# MPPT_POWER.net
KiCad netlist of a schematic drawn in Altium Designer
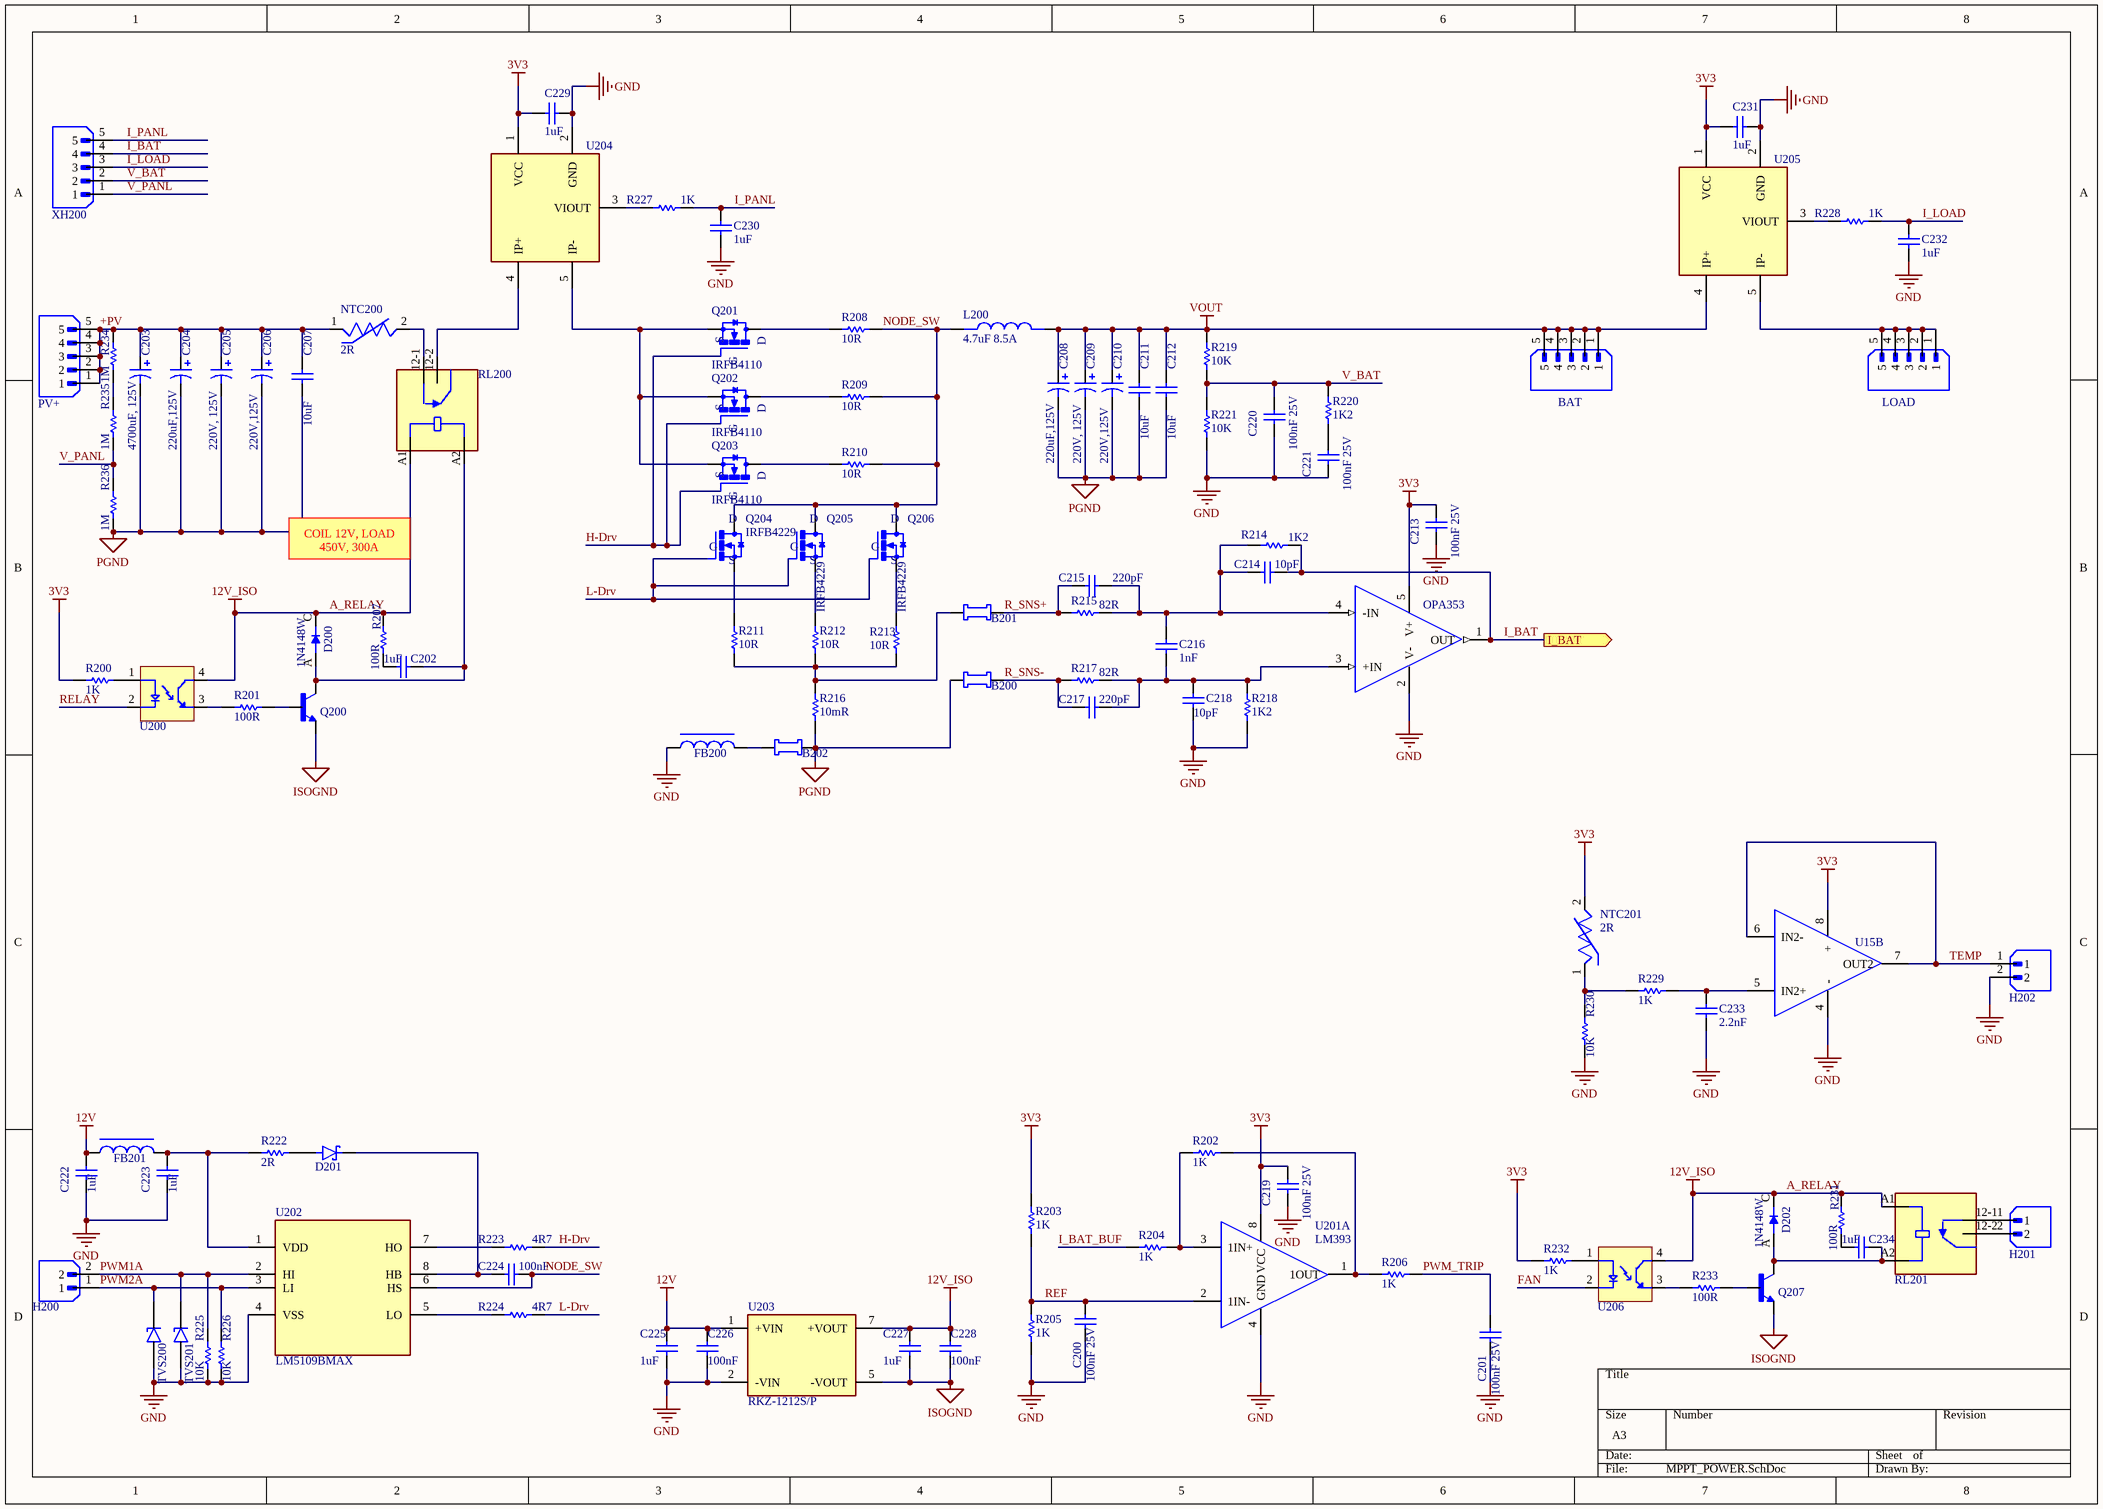
[diagram p0: MPPT_POWER.SchDoc]

(export (version "E")
  (design (tool "Eeschema 10.0.6"))
  (components
    (comp (ref "*") (value "OPA353") (libsource (lib "MPPT_600W") (part "OPA353")))
    (comp (ref "B200")
      (value "Narrow Neck Bridge")
      (footprint "Narrow Bridge")
      (libsource (lib "POWER_PIN_CAMERA") (part "Narrow Neck Bridge"))
    )
    (comp (ref "B201")
      (value "Narrow Neck Bridge")
      (footprint "Narrow Bridge")
      (libsource (lib "POWER_PIN_CAMERA") (part "Narrow Neck Bridge"))
    )
    (comp (ref "B202")
      (value "Narrow Neck Bridge")
      (footprint "Narrow Bridge")
      (libsource (lib "POWER_PIN_CAMERA") (part "Narrow Neck Bridge"))
    )
    (comp (ref "BAT")
      (value "B5B-XH-A(LF)(SN)")
      (footprint "XH2.54 5p")
      (description "Connector Header, XH Series, 5 Position, 2.50mm, Through Hole, Press-Fit, Solder, Natural")
      (fields (field (name "MANUFACTURER") "JST"))
      (libsource (lib "") (part "B5B-XH-A(LF)(SN)_1"))
    )
    (comp (ref "C200")
      (value "100nF 25V")
      (footprint "Cap cer 0603")
      (description "Multilayer Ceramic Capacitor, 0.1 uF, 25 V, ï¿½ 10%, X7R, 0603 [1608 Metric]")
      (fields
        (field (name "MANUFACTURER") "Murata")
        (field (name "MANUFACTURER PART NUMBER") "GCM188R71E104KA57D")
      )
      (libsource (lib "POWER_PIN_CAMERA") (part "GCM188R71E104KA57D"))
    )
    (comp (ref "C201")
      (value "100nF 25V")
      (footprint "Cap cer 0603")
      (description "Multilayer Ceramic Capacitor, 0.1 uF, 25 V, ï¿½ 10%, X7R, 0603 [1608 Metric]")
      (fields
        (field (name "MANUFACTURER") "Murata")
        (field (name "MANUFACTURER PART NUMBER") "GCM188R71E104KA57D")
      )
      (libsource (lib "POWER_PIN_CAMERA") (part "GCM188R71E104KA57D"))
    )
    (comp (ref "C202")
      (value "1uF")
      (footprint "Cap cer 0603")
      (description "Multilayer Ceramic Capacitor, 0.1 uF, 25 V, ï¿½ 10%, X7R, 0603 [1608 Metric]")
      (fields
        (field (name "MANUFACTURER") "Murata")
        (field (name "MANUFACTURER PART NUMBER") "GCM188R71E104KA57D")
      )
      (libsource (lib "POWER_PIN_CAMERA") (part "GCM188R71E104KA57D"))
    )
    (comp (ref "C203")
      (value "4700uF, 125V")
      (footprint "C0805")
      (description "Polarized Capacitor (Surface Mount)")
      (fields (field (name "Comment") "Cap Pol3") (field (name "PUBLISHER") "Altium Limited"))
      (libsource (lib "Miscellaneous Devices") (part "Cap Pol3"))
    )
    (comp (ref "C204")
      (value "220uF,125V")
      (footprint "C0805")
      (description "Polarized Capacitor (Surface Mount)")
      (fields (field (name "Comment") "Cap Pol3") (field (name "PUBLISHER") "Altium Limited"))
      (libsource (lib "Miscellaneous Devices") (part "Cap Pol3"))
    )
    (comp (ref "C205")
      (value "220V, 125V")
      (footprint "C0805")
      (description "Polarized Capacitor (Surface Mount)")
      (fields (field (name "Comment") "Cap Pol3") (field (name "PUBLISHER") "Altium Limited"))
      (libsource (lib "Miscellaneous Devices") (part "Cap Pol3"))
    )
    (comp (ref "C206")
      (value "220V,125V")
      (footprint "C0805")
      (description "Polarized Capacitor (Surface Mount)")
      (fields (field (name "Comment") "Cap Pol3") (field (name "PUBLISHER") "Altium Limited"))
      (libsource (lib "Miscellaneous Devices") (part "Cap Pol3"))
    )
    (comp (ref "C207")
      (value "10uF")
      (footprint "Cap cer 0603")
      (description "Multilayer Ceramic Capacitor, 0.1 uF, 25 V, ï¿½ 10%, X7R, 0603 [1608 Metric]")
      (fields
        (field (name "MANUFACTURER") "Murata")
        (field (name "MANUFACTURER PART NUMBER") "GCM188R71E104KA57D")
      )
      (libsource (lib "POWER_PIN_CAMERA") (part "GCM188R71E104KA57D"))
    )
    (comp (ref "C208")
      (value "220uF,125V")
      (footprint "C0805")
      (description "Polarized Capacitor (Surface Mount)")
      (fields (field (name "Comment") "Cap Pol3") (field (name "PUBLISHER") "Altium Limited"))
      (libsource (lib "Miscellaneous Devices") (part "Cap Pol3"))
    )
    (comp (ref "C209")
      (value "220V, 125V")
      (footprint "C0805")
      (description "Polarized Capacitor (Surface Mount)")
      (fields (field (name "Comment") "Cap Pol3") (field (name "PUBLISHER") "Altium Limited"))
      (libsource (lib "Miscellaneous Devices") (part "Cap Pol3"))
    )
    (comp (ref "C210")
      (value "220V,125V")
      (footprint "C0805")
      (description "Polarized Capacitor (Surface Mount)")
      (fields (field (name "Comment") "Cap Pol3") (field (name "PUBLISHER") "Altium Limited"))
      (libsource (lib "Miscellaneous Devices") (part "Cap Pol3"))
    )
    (comp (ref "C211")
      (value "10uF")
      (footprint "Cap cer 0603")
      (description "Multilayer Ceramic Capacitor, 0.1 uF, 25 V, ï¿½ 10%, X7R, 0603 [1608 Metric]")
      (fields
        (field (name "MANUFACTURER") "Murata")
        (field (name "MANUFACTURER PART NUMBER") "GCM188R71E104KA57D")
      )
      (libsource (lib "POWER_PIN_CAMERA") (part "GCM188R71E104KA57D"))
    )
    (comp (ref "C212")
      (value "10uF")
      (footprint "Cap cer 0603")
      (description "Multilayer Ceramic Capacitor, 0.1 uF, 25 V, ï¿½ 10%, X7R, 0603 [1608 Metric]")
      (fields
        (field (name "MANUFACTURER") "Murata")
        (field (name "MANUFACTURER PART NUMBER") "GCM188R71E104KA57D")
      )
      (libsource (lib "POWER_PIN_CAMERA") (part "GCM188R71E104KA57D"))
    )
    (comp (ref "C213")
      (value "100nF 25V")
      (footprint "Cap cer 0603")
      (description "Multilayer Ceramic Capacitor, 0.1 uF, 25 V, ï¿½ 10%, X7R, 0603 [1608 Metric]")
      (fields
        (field (name "MANUFACTURER") "Murata")
        (field (name "MANUFACTURER PART NUMBER") "GCM188R71E104KA57D")
      )
      (libsource (lib "POWER_PIN_CAMERA") (part "GCM188R71E104KA57D"))
    )
    (comp (ref "C214")
      (value "10pF")
      (footprint "Cap cer 0603")
      (description "Multilayer Ceramic Capacitor, 0.1 uF, 25 V, ï¿½ 10%, X7R, 0603 [1608 Metric]")
      (fields
        (field (name "MANUFACTURER") "Murata")
        (field (name "MANUFACTURER PART NUMBER") "GCM188R71E104KA57D")
      )
      (libsource (lib "POWER_PIN_CAMERA") (part "GCM188R71E104KA57D"))
    )
    (comp (ref "C215")
      (value "220pF")
      (footprint "Cap cer 0603")
      (description "Multilayer Ceramic Capacitor, 0.1 uF, 25 V, ï¿½ 10%, X7R, 0603 [1608 Metric]")
      (fields
        (field (name "MANUFACTURER") "Murata")
        (field (name "MANUFACTURER PART NUMBER") "GCM188R71E104KA57D")
      )
      (libsource (lib "POWER_PIN_CAMERA") (part "GCM188R71E104KA57D"))
    )
    (comp (ref "C216")
      (value "1nF")
      (footprint "Cap cer 0603")
      (description "Multilayer Ceramic Capacitor, 0.1 uF, 25 V, ï¿½ 10%, X7R, 0603 [1608 Metric]")
      (fields
        (field (name "MANUFACTURER") "Murata")
        (field (name "MANUFACTURER PART NUMBER") "GCM188R71E104KA57D")
      )
      (libsource (lib "POWER_PIN_CAMERA") (part "GCM188R71E104KA57D"))
    )
    (comp (ref "C217")
      (value "220pF")
      (footprint "Cap cer 0603")
      (description "Multilayer Ceramic Capacitor, 0.1 uF, 25 V, ï¿½ 10%, X7R, 0603 [1608 Metric]")
      (fields
        (field (name "MANUFACTURER") "Murata")
        (field (name "MANUFACTURER PART NUMBER") "GCM188R71E104KA57D")
      )
      (libsource (lib "POWER_PIN_CAMERA") (part "GCM188R71E104KA57D"))
    )
    (comp (ref "C218")
      (value "10pF")
      (footprint "Cap cer 0603")
      (description "Multilayer Ceramic Capacitor, 0.1 uF, 25 V, ï¿½ 10%, X7R, 0603 [1608 Metric]")
      (fields
        (field (name "MANUFACTURER") "Murata")
        (field (name "MANUFACTURER PART NUMBER") "GCM188R71E104KA57D")
      )
      (libsource (lib "POWER_PIN_CAMERA") (part "GCM188R71E104KA57D"))
    )
    (comp (ref "C219")
      (value "100nF 25V")
      (footprint "Cap cer 0603")
      (description "Multilayer Ceramic Capacitor, 0.1 uF, 25 V, ï¿½ 10%, X7R, 0603 [1608 Metric]")
      (fields
        (field (name "MANUFACTURER") "Murata")
        (field (name "MANUFACTURER PART NUMBER") "GCM188R71E104KA57D")
      )
      (libsource (lib "POWER_PIN_CAMERA") (part "GCM188R71E104KA57D"))
    )
    (comp (ref "C220")
      (value "100nF 25V")
      (footprint "Cap cer 0603")
      (description "Multilayer Ceramic Capacitor, 0.1 uF, 25 V, ï¿½ 10%, X7R, 0603 [1608 Metric]")
      (fields
        (field (name "MANUFACTURER") "Murata")
        (field (name "MANUFACTURER PART NUMBER") "GCM188R71E104KA57D")
      )
      (libsource (lib "POWER_PIN_CAMERA") (part "GCM188R71E104KA57D"))
    )
    (comp (ref "C221")
      (value "100nF 25V")
      (footprint "Cap cer 0603")
      (description "Multilayer Ceramic Capacitor, 0.1 uF, 25 V, ï¿½ 10%, X7R, 0603 [1608 Metric]")
      (fields
        (field (name "MANUFACTURER") "Murata")
        (field (name "MANUFACTURER PART NUMBER") "GCM188R71E104KA57D")
      )
      (libsource (lib "POWER_PIN_CAMERA") (part "GCM188R71E104KA57D"))
    )
    (comp (ref "C222")
      (value "1uF")
      (footprint "Cap cer 0603")
      (description "Multilayer Ceramic Capacitor, 0.1 uF, 25 V, ï¿½ 10%, X7R, 0603 [1608 Metric]")
      (fields
        (field (name "MANUFACTURER") "Murata")
        (field (name "MANUFACTURER PART NUMBER") "GCM188R71E104KA57D")
      )
      (libsource (lib "POWER_PIN_CAMERA") (part "GCM188R71E104KA57D"))
    )
    (comp (ref "C223")
      (value "1uF")
      (footprint "Cap cer 0603")
      (description "Multilayer Ceramic Capacitor, 0.1 uF, 25 V, ï¿½ 10%, X7R, 0603 [1608 Metric]")
      (fields
        (field (name "MANUFACTURER") "Murata")
        (field (name "MANUFACTURER PART NUMBER") "GCM188R71E104KA57D")
      )
      (libsource (lib "POWER_PIN_CAMERA") (part "GCM188R71E104KA57D"))
    )
    (comp (ref "C224")
      (value "100nF")
      (footprint "Cap cer 0603")
      (description "Multilayer Ceramic Capacitor, 0.1 uF, 25 V, ï¿½ 10%, X7R, 0603 [1608 Metric]")
      (fields
        (field (name "MANUFACTURER") "Murata")
        (field (name "MANUFACTURER PART NUMBER") "GCM188R71E104KA57D")
      )
      (libsource (lib "POWER_PIN_CAMERA") (part "GCM188R71E104KA57D"))
    )
    (comp (ref "C225")
      (value "1uF")
      (footprint "Cap cer 0603")
      (description "Multilayer Ceramic Capacitor, 0.1 uF, 25 V, ï¿½ 10%, X7R, 0603 [1608 Metric]")
      (fields
        (field (name "MANUFACTURER") "Murata")
        (field (name "MANUFACTURER PART NUMBER") "GCM188R71E104KA57D")
      )
      (libsource (lib "POWER_PIN_CAMERA") (part "GCM188R71E104KA57D"))
    )
    (comp (ref "C226")
      (value "100nF")
      (footprint "Cap cer 0603")
      (description "Multilayer Ceramic Capacitor, 0.1 uF, 25 V, ï¿½ 10%, X7R, 0603 [1608 Metric]")
      (fields
        (field (name "MANUFACTURER") "Murata")
        (field (name "MANUFACTURER PART NUMBER") "GCM188R71E104KA57D")
      )
      (libsource (lib "POWER_PIN_CAMERA") (part "GCM188R71E104KA57D"))
    )
    (comp (ref "C227")
      (value "1uF")
      (footprint "Cap cer 0603")
      (description "Multilayer Ceramic Capacitor, 0.1 uF, 25 V, ï¿½ 10%, X7R, 0603 [1608 Metric]")
      (fields
        (field (name "MANUFACTURER") "Murata")
        (field (name "MANUFACTURER PART NUMBER") "GCM188R71E104KA57D")
      )
      (libsource (lib "POWER_PIN_CAMERA") (part "GCM188R71E104KA57D"))
    )
    (comp (ref "C228")
      (value "100nF")
      (footprint "Cap cer 0603")
      (description "Multilayer Ceramic Capacitor, 0.1 uF, 25 V, ï¿½ 10%, X7R, 0603 [1608 Metric]")
      (fields
        (field (name "MANUFACTURER") "Murata")
        (field (name "MANUFACTURER PART NUMBER") "GCM188R71E104KA57D")
      )
      (libsource (lib "POWER_PIN_CAMERA") (part "GCM188R71E104KA57D"))
    )
    (comp (ref "C229")
      (value "1uF")
      (footprint "Cap cer 0603")
      (description "Multilayer Ceramic Capacitor, 0.1 uF, 25 V, ï¿½ 10%, X7R, 0603 [1608 Metric]")
      (fields
        (field (name "MANUFACTURER") "Murata")
        (field (name "MANUFACTURER PART NUMBER") "GCM188R71E104KA57D")
      )
      (libsource (lib "POWER_PIN_CAMERA") (part "GCM188R71E104KA57D"))
    )
    (comp (ref "C230")
      (value "1uF")
      (footprint "Cap cer 0603")
      (description "Multilayer Ceramic Capacitor, 0.1 uF, 25 V, ï¿½ 10%, X7R, 0603 [1608 Metric]")
      (fields
        (field (name "MANUFACTURER") "Murata")
        (field (name "MANUFACTURER PART NUMBER") "GCM188R71E104KA57D")
      )
      (libsource (lib "POWER_PIN_CAMERA") (part "GCM188R71E104KA57D"))
    )
    (comp (ref "C231")
      (value "1uF")
      (footprint "Cap cer 0603")
      (description "Multilayer Ceramic Capacitor, 0.1 uF, 25 V, ï¿½ 10%, X7R, 0603 [1608 Metric]")
      (fields
        (field (name "MANUFACTURER") "Murata")
        (field (name "MANUFACTURER PART NUMBER") "GCM188R71E104KA57D")
      )
      (libsource (lib "POWER_PIN_CAMERA") (part "GCM188R71E104KA57D"))
    )
    (comp (ref "C232")
      (value "1uF")
      (footprint "Cap cer 0603")
      (description "Multilayer Ceramic Capacitor, 0.1 uF, 25 V, ï¿½ 10%, X7R, 0603 [1608 Metric]")
      (fields
        (field (name "MANUFACTURER") "Murata")
        (field (name "MANUFACTURER PART NUMBER") "GCM188R71E104KA57D")
      )
      (libsource (lib "POWER_PIN_CAMERA") (part "GCM188R71E104KA57D"))
    )
    (comp (ref "C233")
      (value "2.2nF")
      (footprint "Cap cer 0603")
      (description "Multilayer Ceramic Capacitor, 0.1 uF, 25 V, ï¿½ 10%, X7R, 0603 [1608 Metric]")
      (fields
        (field (name "MANUFACTURER") "Murata")
        (field (name "MANUFACTURER PART NUMBER") "GCM188R71E104KA57D")
      )
      (libsource (lib "POWER_PIN_CAMERA") (part "GCM188R71E104KA57D"))
    )
    (comp (ref "C234")
      (value "1uF")
      (footprint "Cap cer 0603")
      (description "Multilayer Ceramic Capacitor, 0.1 uF, 25 V, ï¿½ 10%, X7R, 0603 [1608 Metric]")
      (fields
        (field (name "MANUFACTURER") "Murata")
        (field (name "MANUFACTURER PART NUMBER") "GCM188R71E104KA57D")
      )
      (libsource (lib "POWER_PIN_CAMERA") (part "GCM188R71E104KA57D"))
    )
    (comp (ref "D200")
      (value "1N4148W")
      (footprint "1N4148")
      (description "Small Signal Diode, Single, 100 V, 300 Ma, 1.25 V, 4 Ns, 2 A Rohs Compliant: Yes")
      (fields (field (name "MANUFACTURER") "Diodes") (field (name "MANUFACTURER PART NUMBER") "1N4148W-7-F"))
      (libsource (lib "POWER_PIN_CAMERA") (part "1N4148W-7-F"))
    )
    (comp (ref "D201")
      (value "B340A-13-F")
      (footprint "B340A")
      (description "Schottky Diode, 3A, 40V, DO-214AC")
      (fields (field (name "MANUFACTURER") "Diodes") (field (name "VOLTAGE") "40V"))
      (libsource (lib "MPPT_600W") (part "B340A-13-F"))
    )
    (comp (ref "D202")
      (value "1N4148W")
      (footprint "1N4148")
      (description "Small Signal Diode, Single, 100 V, 300 Ma, 1.25 V, 4 Ns, 2 A Rohs Compliant: Yes")
      (fields (field (name "MANUFACTURER") "Diodes") (field (name "MANUFACTURER PART NUMBER") "1N4148W-7-F"))
      (libsource (lib "POWER_PIN_CAMERA") (part "1N4148W-7-F"))
    )
    (comp (ref "FB200")
      (value "Ferrite Beads Multi-Layer 390Ohm 25% 100MHz 500mA 300mOhm DCR 0603 Automotive T/R")
      (footprint "FERRITE BEAD 0603")
      (fields
        (field (name "MANUFACTURER") "Murata")
        (field (name "MANUFACTURER PART NUMBER") "BLM18EG391TH1D")
        (field (name "TOLERANCE") "25%")
      )
      (libsource (lib "MPPT_600W") (part "Ferrite Bead"))
    )
    (comp (ref "FB201")
      (value "Ferrite Beads Multi-Layer 390Ohm 25% 100MHz 500mA 300mOhm DCR 0603 Automotive T/R")
      (footprint "FERRITE BEAD 0603")
      (fields
        (field (name "MANUFACTURER") "Murata")
        (field (name "MANUFACTURER PART NUMBER") "BLM18EG391TH1D")
        (field (name "TOLERANCE") "25%")
      )
      (libsource (lib "MPPT_600W") (part "Ferrite Bead"))
    )
    (comp (ref "H200")
      (value "HEADER 2P 2.54")
      (footprint "HEADER 2P 2.544")
      (description "CONNECTOR HEADER, XH SERIES, 2 POSITION, 2.50MM, Press-Fit Solder, Detent Lock, Natural")
      (fields
        (field (name "MANUFACTURER") "JST")
        (field (name "MANUFACTURER PART NUMBER") "B2B-XH-A(LF)(SN)")
      )
      (libsource (lib "MPPT_600W") (part "B2B-XH-A(LF)(SN)"))
    )
    (comp (ref "H201")
      (value "HEADER 2P 2.54")
      (footprint "HEADER 2P 2.544")
      (description "CONNECTOR HEADER, XH SERIES, 2 POSITION, 2.50MM, Press-Fit Solder, Detent Lock, Natural")
      (fields
        (field (name "MANUFACTURER") "JST")
        (field (name "MANUFACTURER PART NUMBER") "B2B-XH-A(LF)(SN)")
      )
      (libsource (lib "") (part "B2B-XH-A(LF)(SN)_1"))
    )
    (comp (ref "H202")
      (value "HEADER 2P 2.54")
      (footprint "HEADER 2P 2.544")
      (description "CONNECTOR HEADER, XH SERIES, 2 POSITION, 2.50MM, Press-Fit Solder, Detent Lock, Natural")
      (fields
        (field (name "MANUFACTURER") "JST")
        (field (name "MANUFACTURER PART NUMBER") "B2B-XH-A(LF)(SN)")
      )
      (libsource (lib "") (part "B2B-XH-A(LF)(SN)_1"))
    )
    (comp (ref "L200")
      (value "4.7uF 8.5A")
      (footprint "Inductor 4.7uF 8.5A")
      (description "FIXED IND 4.7UH 8.5A 18.4MOHM")
      (fields
        (field (name "MANUFACTURER") "Abracon")
        (field (name "MANUFACTURER PART NUMBER") "ASPIAIG-F6050-4R7M-T")
      )
      (libsource (lib "POWER_PIN_CAMERA") (part "Inductor 4.7uF 8.5A"))
    )
    (comp (ref "LOAD")
      (value "B5B-XH-A(LF)(SN)")
      (footprint "XH2.54 5p")
      (description "Connector Header, XH Series, 5 Position, 2.50mm, Through Hole, Press-Fit, Solder, Natural")
      (fields (field (name "MANUFACTURER") "JST"))
      (libsource (lib "") (part "B5B-XH-A(LF)(SN)_1"))
    )
    (comp (ref "NTC200") (value "2R") (libsource (lib "MPPT_600W") (part "NTC")))
    (comp (ref "NTC201") (value "2R") (libsource (lib "MPPT_600W") (part "NTC")))
    (comp (ref "PV+")
      (value "B5B-XH-A(LF)(SN)")
      (footprint "XH2.54 5p")
      (description "Connector Header, XH Series, 5 Position, 2.50mm, Through Hole, Press-Fit, Solder, Natural")
      (fields (field (name "MANUFACTURER") "JST"))
      (libsource (lib "MPPT_600W") (part "B5B-XH-A(LF)(SN)"))
    )
    (comp (ref "Q200")
      (value "MMBT3904")
      (footprint "MMBT3904")
      (description "MMBT3904 Series 40 V CE Breakdown 0.2 A NPN General Purpose Amplifier - SOT-23")
      (fields (field (name "MANUFACTURER") "onsemi"))
      (libsource (lib "MPPT_600W") (part "MMBT3904"))
    )
    (comp (ref "Q201") (value "IRFB4110") (libsource (lib "MPPT_600W") (part "MOSFET")))
    (comp (ref "Q202") (value "IRFB4110") (libsource (lib "MPPT_600W") (part "MOSFET")))
    (comp (ref "Q203") (value "IRFB4110") (libsource (lib "MPPT_600W") (part "MOSFET")))
    (comp (ref "Q204") (value "IRFB4229") (libsource (lib "MPPT_600W") (part "MOSFET")))
    (comp (ref "Q205") (value "IRFB4229") (libsource (lib "MPPT_600W") (part "MOSFET")))
    (comp (ref "Q206") (value "IRFB4229") (libsource (lib "MPPT_600W") (part "MOSFET")))
    (comp (ref "Q207")
      (value "MMBT3904")
      (footprint "MMBT3904")
      (description "MMBT3904 Series 40 V CE Breakdown 0.2 A NPN General Purpose Amplifier - SOT-23")
      (fields (field (name "MANUFACTURER") "onsemi"))
      (libsource (lib "MPPT_600W") (part "MMBT3904"))
    )
    (comp (ref "R200")
      (value "1K")
      (footprint "Res 0603")
      (description "Res Thick Film 0603 2.2K Ohm 5% 1/10W ±200ppm/°C Molded SMD SMD Paper T/R")
      (fields
        (field (name "MANUFACTURER") "Vishay")
        (field (name "MANUFACTURER PART NUMBER") "CRCW06032K20JNEA")
      )
      (libsource (lib "POWER_PIN_CAMERA") (part "Resistor 2.2K"))
    )
    (comp (ref "R201")
      (value "100R")
      (footprint "Res 0603")
      (description "Res Thick Film 0603 2.2K Ohm 5% 1/10W ±200ppm/°C Molded SMD SMD Paper T/R")
      (fields
        (field (name "MANUFACTURER") "Vishay")
        (field (name "MANUFACTURER PART NUMBER") "CRCW06032K20JNEA")
      )
      (libsource (lib "POWER_PIN_CAMERA") (part "Resistor 2.2K"))
    )
    (comp (ref "R202")
      (value "1K")
      (footprint "Res 0603")
      (description "Res Thick Film 0603 2.2K Ohm 5% 1/10W ±200ppm/°C Molded SMD SMD Paper T/R")
      (fields
        (field (name "MANUFACTURER") "Vishay")
        (field (name "MANUFACTURER PART NUMBER") "CRCW06032K20JNEA")
      )
      (libsource (lib "POWER_PIN_CAMERA") (part "Resistor 2.2K"))
    )
    (comp (ref "R203")
      (value "1K")
      (footprint "Res 0603")
      (description "Res Thick Film 0603 2.2K Ohm 5% 1/10W ±200ppm/°C Molded SMD SMD Paper T/R")
      (fields
        (field (name "MANUFACTURER") "Vishay")
        (field (name "MANUFACTURER PART NUMBER") "CRCW06032K20JNEA")
      )
      (libsource (lib "POWER_PIN_CAMERA") (part "Resistor 2.2K"))
    )
    (comp (ref "R204")
      (value "1K")
      (footprint "Res 0603")
      (description "Res Thick Film 0603 2.2K Ohm 5% 1/10W ±200ppm/°C Molded SMD SMD Paper T/R")
      (fields
        (field (name "MANUFACTURER") "Vishay")
        (field (name "MANUFACTURER PART NUMBER") "CRCW06032K20JNEA")
      )
      (libsource (lib "POWER_PIN_CAMERA") (part "Resistor 2.2K"))
    )
    (comp (ref "R205")
      (value "1K")
      (footprint "Res 0603")
      (description "Res Thick Film 0603 2.2K Ohm 5% 1/10W ±200ppm/°C Molded SMD SMD Paper T/R")
      (fields
        (field (name "MANUFACTURER") "Vishay")
        (field (name "MANUFACTURER PART NUMBER") "CRCW06032K20JNEA")
      )
      (libsource (lib "POWER_PIN_CAMERA") (part "Resistor 2.2K"))
    )
    (comp (ref "R206")
      (value "1K")
      (footprint "Res 0603")
      (description "Res Thick Film 0603 2.2K Ohm 5% 1/10W ±200ppm/°C Molded SMD SMD Paper T/R")
      (fields
        (field (name "MANUFACTURER") "Vishay")
        (field (name "MANUFACTURER PART NUMBER") "CRCW06032K20JNEA")
      )
      (libsource (lib "POWER_PIN_CAMERA") (part "Resistor 2.2K"))
    )
    (comp (ref "R207")
      (value "100R")
      (footprint "Res 0603")
      (description "Res Thick Film 0603 2.2K Ohm 5% 1/10W ±200ppm/°C Molded SMD SMD Paper T/R")
      (fields
        (field (name "MANUFACTURER") "Vishay")
        (field (name "MANUFACTURER PART NUMBER") "CRCW06032K20JNEA")
      )
      (libsource (lib "POWER_PIN_CAMERA") (part "Resistor 2.2K"))
    )
    (comp (ref "R208")
      (value "10R")
      (footprint "Res 0603")
      (description "Res Thick Film 0603 2.2K Ohm 5% 1/10W ±200ppm/°C Molded SMD SMD Paper T/R")
      (fields
        (field (name "MANUFACTURER") "Vishay")
        (field (name "MANUFACTURER PART NUMBER") "CRCW06032K20JNEA")
      )
      (libsource (lib "POWER_PIN_CAMERA") (part "Resistor 2.2K"))
    )
    (comp (ref "R209")
      (value "10R")
      (footprint "Res 0603")
      (description "Res Thick Film 0603 2.2K Ohm 5% 1/10W ±200ppm/°C Molded SMD SMD Paper T/R")
      (fields
        (field (name "MANUFACTURER") "Vishay")
        (field (name "MANUFACTURER PART NUMBER") "CRCW06032K20JNEA")
      )
      (libsource (lib "POWER_PIN_CAMERA") (part "Resistor 2.2K"))
    )
    (comp (ref "R210")
      (value "10R")
      (footprint "Res 0603")
      (description "Res Thick Film 0603 2.2K Ohm 5% 1/10W ±200ppm/°C Molded SMD SMD Paper T/R")
      (fields
        (field (name "MANUFACTURER") "Vishay")
        (field (name "MANUFACTURER PART NUMBER") "CRCW06032K20JNEA")
      )
      (libsource (lib "POWER_PIN_CAMERA") (part "Resistor 2.2K"))
    )
    (comp (ref "R211")
      (value "10R")
      (footprint "Res 0603")
      (description "Res Thick Film 0603 2.2K Ohm 5% 1/10W ±200ppm/°C Molded SMD SMD Paper T/R")
      (fields
        (field (name "MANUFACTURER") "Vishay")
        (field (name "MANUFACTURER PART NUMBER") "CRCW06032K20JNEA")
      )
      (libsource (lib "POWER_PIN_CAMERA") (part "Resistor 2.2K"))
    )
    (comp (ref "R212")
      (value "10R")
      (footprint "Res 0603")
      (description "Res Thick Film 0603 2.2K Ohm 5% 1/10W ±200ppm/°C Molded SMD SMD Paper T/R")
      (fields
        (field (name "MANUFACTURER") "Vishay")
        (field (name "MANUFACTURER PART NUMBER") "CRCW06032K20JNEA")
      )
      (libsource (lib "POWER_PIN_CAMERA") (part "Resistor 2.2K"))
    )
    (comp (ref "R213")
      (value "10R")
      (footprint "Res 0603")
      (description "Res Thick Film 0603 2.2K Ohm 5% 1/10W ±200ppm/°C Molded SMD SMD Paper T/R")
      (fields
        (field (name "MANUFACTURER") "Vishay")
        (field (name "MANUFACTURER PART NUMBER") "CRCW06032K20JNEA")
      )
      (libsource (lib "POWER_PIN_CAMERA") (part "Resistor 2.2K"))
    )
    (comp (ref "R214")
      (value "1K2")
      (footprint "Res 0603")
      (description "Res Thick Film 0603 2.2K Ohm 5% 1/10W ±200ppm/°C Molded SMD SMD Paper T/R")
      (fields
        (field (name "MANUFACTURER") "Vishay")
        (field (name "MANUFACTURER PART NUMBER") "CRCW06032K20JNEA")
      )
      (libsource (lib "POWER_PIN_CAMERA") (part "Resistor 2.2K"))
    )
    (comp (ref "R215")
      (value "82R")
      (footprint "Res 0603")
      (description "Res Thick Film 0603 2.2K Ohm 5% 1/10W ±200ppm/°C Molded SMD SMD Paper T/R")
      (fields
        (field (name "MANUFACTURER") "Vishay")
        (field (name "MANUFACTURER PART NUMBER") "CRCW06032K20JNEA")
      )
      (libsource (lib "POWER_PIN_CAMERA") (part "Resistor 2.2K"))
    )
    (comp (ref "R216")
      (value "10mR")
      (footprint "Res 0603")
      (description "Res Thick Film 0603 2.2K Ohm 5% 1/10W ±200ppm/°C Molded SMD SMD Paper T/R")
      (fields
        (field (name "MANUFACTURER") "Vishay")
        (field (name "MANUFACTURER PART NUMBER") "CRCW06032K20JNEA")
      )
      (libsource (lib "POWER_PIN_CAMERA") (part "Resistor 2.2K"))
    )
    (comp (ref "R217")
      (value "82R")
      (footprint "Res 0603")
      (description "Res Thick Film 0603 2.2K Ohm 5% 1/10W ±200ppm/°C Molded SMD SMD Paper T/R")
      (fields
        (field (name "MANUFACTURER") "Vishay")
        (field (name "MANUFACTURER PART NUMBER") "CRCW06032K20JNEA")
      )
      (libsource (lib "POWER_PIN_CAMERA") (part "Resistor 2.2K"))
    )
    (comp (ref "R218")
      (value "1K2")
      (footprint "Res 0603")
      (description "Res Thick Film 0603 2.2K Ohm 5% 1/10W ±200ppm/°C Molded SMD SMD Paper T/R")
      (fields
        (field (name "MANUFACTURER") "Vishay")
        (field (name "MANUFACTURER PART NUMBER") "CRCW06032K20JNEA")
      )
      (libsource (lib "POWER_PIN_CAMERA") (part "Resistor 2.2K"))
    )
    (comp (ref "R219")
      (value "10K")
      (footprint "Res 0603")
      (description "Res Thick Film 0603 2.2K Ohm 5% 1/10W ±200ppm/°C Molded SMD SMD Paper T/R")
      (fields
        (field (name "MANUFACTURER") "Vishay")
        (field (name "MANUFACTURER PART NUMBER") "CRCW06032K20JNEA")
      )
      (libsource (lib "POWER_PIN_CAMERA") (part "Resistor 2.2K"))
    )
    (comp (ref "R220")
      (value "1K2")
      (footprint "Res 0603")
      (description "Res Thick Film 0603 2.2K Ohm 5% 1/10W ±200ppm/°C Molded SMD SMD Paper T/R")
      (fields
        (field (name "MANUFACTURER") "Vishay")
        (field (name "MANUFACTURER PART NUMBER") "CRCW06032K20JNEA")
      )
      (libsource (lib "POWER_PIN_CAMERA") (part "Resistor 2.2K"))
    )
    (comp (ref "R221")
      (value "10K")
      (footprint "Res 0603")
      (description "Res Thick Film 0603 2.2K Ohm 5% 1/10W ±200ppm/°C Molded SMD SMD Paper T/R")
      (fields
        (field (name "MANUFACTURER") "Vishay")
        (field (name "MANUFACTURER PART NUMBER") "CRCW06032K20JNEA")
      )
      (libsource (lib "POWER_PIN_CAMERA") (part "Resistor 2.2K"))
    )
    (comp (ref "R222")
      (value "2R")
      (footprint "Res 0603")
      (description "Res Thick Film 0603 2.2K Ohm 5% 1/10W ±200ppm/°C Molded SMD SMD Paper T/R")
      (fields
        (field (name "MANUFACTURER") "Vishay")
        (field (name "MANUFACTURER PART NUMBER") "CRCW06032K20JNEA")
      )
      (libsource (lib "POWER_PIN_CAMERA") (part "Resistor 2.2K"))
    )
    (comp (ref "R223")
      (value "4R7")
      (footprint "Res 0603")
      (description "Res Thick Film 0603 2.2K Ohm 5% 1/10W ±200ppm/°C Molded SMD SMD Paper T/R")
      (fields
        (field (name "MANUFACTURER") "Vishay")
        (field (name "MANUFACTURER PART NUMBER") "CRCW06032K20JNEA")
      )
      (libsource (lib "POWER_PIN_CAMERA") (part "Resistor 2.2K"))
    )
    (comp (ref "R224")
      (value "4R7")
      (footprint "Res 0603")
      (description "Res Thick Film 0603 2.2K Ohm 5% 1/10W ±200ppm/°C Molded SMD SMD Paper T/R")
      (fields
        (field (name "MANUFACTURER") "Vishay")
        (field (name "MANUFACTURER PART NUMBER") "CRCW06032K20JNEA")
      )
      (libsource (lib "POWER_PIN_CAMERA") (part "Resistor 2.2K"))
    )
    (comp (ref "R225")
      (value "10K")
      (footprint "Res 0603")
      (description "Res Thick Film 0603 2.2K Ohm 5% 1/10W ±200ppm/°C Molded SMD SMD Paper T/R")
      (fields
        (field (name "MANUFACTURER") "Vishay")
        (field (name "MANUFACTURER PART NUMBER") "CRCW06032K20JNEA")
      )
      (libsource (lib "POWER_PIN_CAMERA") (part "Resistor 2.2K"))
    )
    (comp (ref "R226")
      (value "10K")
      (footprint "Res 0603")
      (description "Res Thick Film 0603 2.2K Ohm 5% 1/10W ±200ppm/°C Molded SMD SMD Paper T/R")
      (fields
        (field (name "MANUFACTURER") "Vishay")
        (field (name "MANUFACTURER PART NUMBER") "CRCW06032K20JNEA")
      )
      (libsource (lib "POWER_PIN_CAMERA") (part "Resistor 2.2K"))
    )
    (comp (ref "R227")
      (value "1K")
      (footprint "Res 0603")
      (description "Res Thick Film 0603 2.2K Ohm 5% 1/10W ±200ppm/°C Molded SMD SMD Paper T/R")
      (fields
        (field (name "MANUFACTURER") "Vishay")
        (field (name "MANUFACTURER PART NUMBER") "CRCW06032K20JNEA")
      )
      (libsource (lib "POWER_PIN_CAMERA") (part "Resistor 2.2K"))
    )
    (comp (ref "R228")
      (value "1K")
      (footprint "Res 0603")
      (description "Res Thick Film 0603 2.2K Ohm 5% 1/10W ±200ppm/°C Molded SMD SMD Paper T/R")
      (fields
        (field (name "MANUFACTURER") "Vishay")
        (field (name "MANUFACTURER PART NUMBER") "CRCW06032K20JNEA")
      )
      (libsource (lib "POWER_PIN_CAMERA") (part "Resistor 2.2K"))
    )
    (comp (ref "R229")
      (value "1K")
      (footprint "Res 0603")
      (description "Res Thick Film 0603 2.2K Ohm 5% 1/10W ±200ppm/°C Molded SMD SMD Paper T/R")
      (fields
        (field (name "MANUFACTURER") "Vishay")
        (field (name "MANUFACTURER PART NUMBER") "CRCW06032K20JNEA")
      )
      (libsource (lib "POWER_PIN_CAMERA") (part "Resistor 2.2K"))
    )
    (comp (ref "R230")
      (value "10K")
      (footprint "Res 0603")
      (description "Res Thick Film 0603 2.2K Ohm 5% 1/10W ±200ppm/°C Molded SMD SMD Paper T/R")
      (fields
        (field (name "MANUFACTURER") "Vishay")
        (field (name "MANUFACTURER PART NUMBER") "CRCW06032K20JNEA")
      )
      (libsource (lib "POWER_PIN_CAMERA") (part "Resistor 2.2K"))
    )
    (comp (ref "R231")
      (value "100R")
      (footprint "Res 0603")
      (description "Res Thick Film 0603 2.2K Ohm 5% 1/10W ±200ppm/°C Molded SMD SMD Paper T/R")
      (fields
        (field (name "MANUFACTURER") "Vishay")
        (field (name "MANUFACTURER PART NUMBER") "CRCW06032K20JNEA")
      )
      (libsource (lib "POWER_PIN_CAMERA") (part "Resistor 2.2K"))
    )
    (comp (ref "R232")
      (value "1K")
      (footprint "Res 0603")
      (description "Res Thick Film 0603 2.2K Ohm 5% 1/10W ±200ppm/°C Molded SMD SMD Paper T/R")
      (fields
        (field (name "MANUFACTURER") "Vishay")
        (field (name "MANUFACTURER PART NUMBER") "CRCW06032K20JNEA")
      )
      (libsource (lib "POWER_PIN_CAMERA") (part "Resistor 2.2K"))
    )
    (comp (ref "R233")
      (value "100R")
      (footprint "Res 0603")
      (description "Res Thick Film 0603 2.2K Ohm 5% 1/10W ±200ppm/°C Molded SMD SMD Paper T/R")
      (fields
        (field (name "MANUFACTURER") "Vishay")
        (field (name "MANUFACTURER PART NUMBER") "CRCW06032K20JNEA")
      )
      (libsource (lib "POWER_PIN_CAMERA") (part "Resistor 2.2K"))
    )
    (comp (ref "R234")
      (value "1M")
      (footprint "Res 0603")
      (description "Res Thick Film 0603 2.2K Ohm 5% 1/10W ±200ppm/°C Molded SMD SMD Paper T/R")
      (fields
        (field (name "MANUFACTURER") "Vishay")
        (field (name "MANUFACTURER PART NUMBER") "CRCW06032K20JNEA")
      )
      (libsource (lib "POWER_PIN_CAMERA") (part "Resistor 2.2K"))
    )
    (comp (ref "R235")
      (value "1M")
      (footprint "Res 0603")
      (description "Res Thick Film 0603 2.2K Ohm 5% 1/10W ±200ppm/°C Molded SMD SMD Paper T/R")
      (fields
        (field (name "MANUFACTURER") "Vishay")
        (field (name "MANUFACTURER PART NUMBER") "CRCW06032K20JNEA")
      )
      (libsource (lib "POWER_PIN_CAMERA") (part "Resistor 2.2K"))
    )
    (comp (ref "R236")
      (value "1M")
      (footprint "Res 0603")
      (description "Res Thick Film 0603 2.2K Ohm 5% 1/10W ±200ppm/°C Molded SMD SMD Paper T/R")
      (fields
        (field (name "MANUFACTURER") "Vishay")
        (field (name "MANUFACTURER PART NUMBER") "CRCW06032K20JNEA")
      )
      (libsource (lib "POWER_PIN_CAMERA") (part "Resistor 2.2K"))
    )
    (comp (ref "RL200")
      (value "~")
      (description "COIL 12, LOAD 450V, 300A")
      (libsource (lib "") (part "HFE-Relay_1"))
    )
    (comp (ref "RL201")
      (value "~")
      (description "COIL 12, LOAD 450V, 300A")
      (libsource (lib "MPPT_600W") (part "HFE-Relay"))
    )
    (comp (ref "TVS200")
      (value "SMCJ5.0A-13-F")
      (footprint "TVS 5V")
      (description "SMCJ5.0A Series 1500 W 5.0 V Surface Mount Uni-Directional TVS Diode - DO-214AB")
      (fields (field (name "MANUFACTURER") "Diodes"))
      (libsource (lib "MPPT_600W") (part "SMCJ5.0A-13-F"))
    )
    (comp (ref "TVS201")
      (value "SMCJ5.0A-13-F")
      (footprint "TVS 5V")
      (description "SMCJ5.0A Series 1500 W 5.0 V Surface Mount Uni-Directional TVS Diode - DO-214AB")
      (fields (field (name "MANUFACTURER") "Diodes"))
      (libsource (lib "MPPT_600W") (part "SMCJ5.0A-13-F"))
    )
    (comp (ref "U15")
      (value "LM358DT")
      (footprint "LM358")
      (description "Operational Amplifier, 2-Channels, 1.1 MHz, 0.6 V/us, 3 V to 30 V, 8 Pins, SOIC")
      (fields (field (name "MANUFACTURER") "STMicroelectronics"))
      (libsource (lib "MPPT_600W") (part "LM358DT"))
    )
    (comp (ref "U200")
      (value "PC817X1NIP1B")
      (footprint "PC817")
      (description "Optocoupler Dc-in 1-CH Transistor Dc-out 4-PIN DIP SMD T/r")
      (fields (field (name "MANUFACTURER") "Sharp"))
      (libsource (lib "MPPT_600W") (part "PC817X1NIP1B"))
    )
    (comp (ref "U201")
      (value "LM393")
      (footprint "lm393")
      (description "LM393 Series Dual 36 V 250 nA SMT Low Power Voltage Comparator - SOIC-8")
      (fields
        (field (name "MANUFACTURER") "STMicroelectronics")
        (field (name "MANUFACTURER PART NUMBER") "LM393DT")
      )
      (libsource (lib "MPPT_600W") (part "LM393DT"))
    )
    (comp (ref "U202")
      (value "LM5109BMAX")
      (footprint "LM5109B")
      (description "1-A, 100-V half bridge gate driver with 8-V UVLO and high noise immunity 8-SOIC -40 to 125")
      (fields
        (field (name "MANUFACTURER") "TI National Semiconductor")
        (field (name "MANUFACTURER PART NUMBER") "LM5109BMAX/NOPB")
      )
      (libsource (lib "MPPT_600W") (part "LM5109BMAX/NOPB"))
    )
    (comp (ref "U203")
      (value "RKZ-1212S/P")
      (footprint "1212S")
      (description "2W DC/DC-Converter 'ECONOLINE' SIP7 3kV unreg; V. In: 12; V. Out: 12; mA. Out: 168")
      (fields (field (name "MANUFACTURER") "Recom"))
      (libsource (lib "MPPT_600W") (part "RKZ-1212S/P"))
    )
    (comp (ref "U204")
      (value "ACS758LCB-100U-PFF-T")
      (footprint "ACS758")
      (description "Open Loop Current Sensor AC/DC Current 5V Automotive 5-Pin Case CB-PFF Tube")
      (fields (field (name "MANUFACTURER") "Allegro MicroSystems"))
      (libsource (lib "MPPT_600W") (part "ACS758LCB-100U-PFF-T"))
    )
    (comp (ref "U205")
      (value "ACS758LCB-100U-PFF-T")
      (footprint "ACS758")
      (description "Open Loop Current Sensor AC/DC Current 5V Automotive 5-Pin Case CB-PFF Tube")
      (fields (field (name "MANUFACTURER") "Allegro MicroSystems"))
      (libsource (lib "MPPT_600W") (part "ACS758LCB-100U-PFF-T"))
    )
    (comp (ref "U206")
      (value "PC817X1NIP1B")
      (footprint "PC817")
      (description "Optocoupler Dc-in 1-CH Transistor Dc-out 4-PIN DIP SMD T/r")
      (fields (field (name "MANUFACTURER") "Sharp"))
      (libsource (lib "MPPT_600W") (part "PC817X1NIP1B"))
    )
    (comp (ref "XH200")
      (value "B5B-XH-A(LF)(SN)")
      (footprint "XH2.54 5p")
      (description "Connector Header, XH Series, 5 Position, 2.50mm, Through Hole, Press-Fit, Solder, Natural")
      (fields (field (name "MANUFACTURER") "JST"))
      (libsource (lib "MPPT_600W") (part "B5B-XH-A(LF)(SN)"))
    )
  )
  (nets
    (net (code "1") (name "/+PV") (class "Default")
      (node (ref "C203") (pin "1") (pinfunction "1_1") (pintype "passive"))
      (node (ref "C204") (pin "1") (pinfunction "1_1") (pintype "passive"))
      (node (ref "C205") (pin "1") (pinfunction "1_1") (pintype "passive"))
      (node (ref "C206") (pin "1") (pinfunction "1_1") (pintype "passive"))
      (node (ref "C207") (pin "1") (pinfunction "1_1") (pintype "passive"))
      (node (ref "NTC200") (pin "1") (pinfunction "1_1") (pintype "passive"))
      (node (ref "PV+") (pin "1") (pinfunction "1_1") (pintype "passive"))
      (node (ref "PV+") (pin "2") (pinfunction "2_2") (pintype "passive"))
      (node (ref "PV+") (pin "3") (pinfunction "3_3") (pintype "passive"))
      (node (ref "PV+") (pin "4") (pinfunction "4_4") (pintype "passive"))
      (node (ref "PV+") (pin "5") (pinfunction "5_5") (pintype "passive"))
      (node (ref "R234") (pin "2") (pinfunction "2_2") (pintype "passive"))
    )
    (net (code "2") (name "/FAN") (class "Default")
      (node (ref "U206") (pin "2") (pinfunction "C_2") (pintype "passive"))
    )
    (net (code "3") (name "/H-Drv") (class "Default")
      (node (ref "Q201") (pin "1") (pinfunction "G_1") (pintype "passive"))
      (node (ref "Q202") (pin "1") (pinfunction "G_1") (pintype "passive"))
      (node (ref "Q203") (pin "1") (pinfunction "G_1") (pintype "passive"))
      (node (ref "R223") (pin "1") (pinfunction "1_1") (pintype "passive"))
    )
    (net (code "4") (name "/I_BAT") (class "Default")
      (node (ref "*") (pin "1") (pinfunction "OUT_1") (pintype "output"))
      (node (ref "C214") (pin "2") (pinfunction "2_2") (pintype "passive"))
      (node (ref "R214") (pin "1") (pinfunction "1_1") (pintype "passive"))
      (node (ref "XH200") (pin "4") (pinfunction "4_4") (pintype "passive"))
    )
    (net (code "5") (name "/I_BAT_BUF") (class "Default")
      (node (ref "R204") (pin "1") (pinfunction "1_1") (pintype "passive"))
    )
    (net (code "6") (name "/I_LOAD") (class "Default")
      (node (ref "C232") (pin "2") (pinfunction "2_2") (pintype "passive"))
      (node (ref "R228") (pin "1") (pinfunction "1_1") (pintype "passive"))
      (node (ref "XH200") (pin "3") (pinfunction "3_3") (pintype "passive"))
    )
    (net (code "7") (name "/I_PANL") (class "Default")
      (node (ref "C230") (pin "2") (pinfunction "2_2") (pintype "passive"))
      (node (ref "R227") (pin "1") (pinfunction "1_1") (pintype "passive"))
      (node (ref "XH200") (pin "5") (pinfunction "5_5") (pintype "passive"))
    )
    (net (code "8") (name "/L-Drv") (class "Default")
      (node (ref "Q204") (pin "1") (pinfunction "G_1") (pintype "passive"))
      (node (ref "Q205") (pin "1") (pinfunction "G_1") (pintype "passive"))
      (node (ref "Q206") (pin "1") (pinfunction "G_1") (pintype "passive"))
      (node (ref "R224") (pin "1") (pinfunction "1_1") (pintype "passive"))
    )
    (net (code "9") (name "/NODE_SW") (class "Default")
      (node (ref "C224") (pin "1") (pinfunction "1_1") (pintype "passive"))
      (node (ref "L200") (pin "1") (pinfunction "1_1") (pintype "passive"))
      (node (ref "Q204") (pin "2") (pinfunction "D_2") (pintype "passive"))
      (node (ref "Q205") (pin "2") (pinfunction "D_2") (pintype "passive"))
      (node (ref "Q206") (pin "2") (pinfunction "D_2") (pintype "passive"))
      (node (ref "R208") (pin "2") (pinfunction "2_2") (pintype "passive"))
      (node (ref "R209") (pin "2") (pinfunction "2_2") (pintype "passive"))
      (node (ref "R210") (pin "2") (pinfunction "2_2") (pintype "passive"))
      (node (ref "U202") (pin "6") (pinfunction "HS_6") (pintype "passive"))
    )
    (net (code "10") (name "/PWM1A") (class "Default")
      (node (ref "H200") (pin "2") (pinfunction "2_2") (pintype "passive"))
      (node (ref "R225") (pin "2") (pinfunction "2_2") (pintype "passive"))
      (node (ref "TVS201") (pin "1") (pinfunction "C_1") (pintype "passive"))
      (node (ref "U202") (pin "2") (pinfunction "HI_2") (pintype "passive"))
    )
    (net (code "11") (name "/PWM2A") (class "Default")
      (node (ref "H200") (pin "1") (pinfunction "1_1") (pintype "passive"))
      (node (ref "R226") (pin "2") (pinfunction "2_2") (pintype "passive"))
      (node (ref "TVS200") (pin "1") (pinfunction "C_1") (pintype "passive"))
      (node (ref "U202") (pin "3") (pinfunction "LI_3") (pintype "passive"))
    )
    (net (code "12") (name "/PWM_TRIP") (class "Default")
      (node (ref "C201") (pin "2") (pinfunction "2_2") (pintype "passive"))
      (node (ref "R206") (pin "2") (pinfunction "2_2") (pintype "passive"))
    )
    (net (code "13") (name "/REF") (class "Default")
      (node (ref "C200") (pin "2") (pinfunction "2_2") (pintype "passive"))
      (node (ref "R203") (pin "1") (pinfunction "1_1") (pintype "passive"))
      (node (ref "R205") (pin "2") (pinfunction "2_2") (pintype "passive"))
      (node (ref "U201") (pin "2") (pinfunction "1IN-_2") (pintype "passive"))
    )
    (net (code "14") (name "/RELAY") (class "Default")
      (node (ref "U200") (pin "2") (pinfunction "C_2") (pintype "passive"))
    )
    (net (code "15") (name "/R_SNS+") (class "Default")
      (node (ref "B201") (pin "2") (pinfunction "2_2") (pintype "passive"))
      (node (ref "C215") (pin "2") (pinfunction "2_2") (pintype "passive"))
      (node (ref "R215") (pin "1") (pinfunction "1_1") (pintype "passive"))
    )
    (net (code "16") (name "/R_SNS-") (class "Default")
      (node (ref "B200") (pin "2") (pinfunction "2_2") (pintype "passive"))
      (node (ref "C217") (pin "2") (pinfunction "2_2") (pintype "passive"))
      (node (ref "R217") (pin "1") (pinfunction "1_1") (pintype "passive"))
    )
    (net (code "17") (name "/TEMP") (class "Default")
      (node (ref "H202") (pin "1") (pinfunction "1_1") (pintype "passive"))
      (node (ref "U15") (pin "6") (pinfunction "IN2-_6") (pintype "passive"))
      (node (ref "U15") (pin "7") (pinfunction "OUT2_7") (pintype "passive"))
    )
    (net (code "18") (name "/V_BAT") (class "Default")
      (node (ref "C220") (pin "2") (pinfunction "2_2") (pintype "passive"))
      (node (ref "R219") (pin "1") (pinfunction "1_1") (pintype "passive"))
      (node (ref "R220") (pin "1") (pinfunction "1_1") (pintype "passive"))
      (node (ref "R221") (pin "2") (pinfunction "2_2") (pintype "passive"))
      (node (ref "XH200") (pin "2") (pinfunction "2_2") (pintype "passive"))
    )
    (net (code "19") (name "/V_PANL") (class "Default")
      (node (ref "R235") (pin "1") (pinfunction "1_1") (pintype "passive"))
      (node (ref "R236") (pin "2") (pinfunction "2_2") (pintype "passive"))
      (node (ref "XH200") (pin "1") (pinfunction "1_1") (pintype "passive"))
    )
    (net (code "20") (name "3V3") (class "Default")
      (node (ref "*") (pin "5") (pinfunction "V+_5") (pintype "power_in"))
      (node (ref "C213") (pin "2") (pinfunction "2_2") (pintype "passive"))
      (node (ref "C219") (pin "2") (pinfunction "2_2") (pintype "passive"))
      (node (ref "C229") (pin "2") (pinfunction "2_2") (pintype "passive"))
      (node (ref "C231") (pin "2") (pinfunction "2_2") (pintype "passive"))
      (node (ref "NTC201") (pin "2") (pinfunction "2_2") (pintype "passive"))
      (node (ref "R200") (pin "1") (pinfunction "1_1") (pintype "passive"))
      (node (ref "R203") (pin "2") (pinfunction "2_2") (pintype "passive"))
      (node (ref "R232") (pin "1") (pinfunction "1_1") (pintype "passive"))
      (node (ref "U15") (pin "8") (pinfunction "+_8") (pintype "passive"))
      (node (ref "U201") (pin "8") (pinfunction "VCC_8") (pintype "passive"))
      (node (ref "U204") (pin "1") (pinfunction "VCC_1") (pintype "power_in"))
      (node (ref "U205") (pin "1") (pinfunction "VCC_1") (pintype "power_in"))
    )
    (net (code "21") (name "12V") (class "Default")
      (node (ref "C222") (pin "2") (pinfunction "2_2") (pintype "passive"))
      (node (ref "C225") (pin "1") (pinfunction "1_1") (pintype "passive"))
      (node (ref "C226") (pin "1") (pinfunction "1_1") (pintype "passive"))
      (node (ref "FB201") (pin "1") (pinfunction "1_1") (pintype "passive"))
      (node (ref "U203") (pin "1") (pinfunction "+VIN_1") (pintype "passive"))
    )
    (net (code "22") (name "12V_ISO") (class "Default")
      (node (ref "C227") (pin "1") (pinfunction "1_1") (pintype "passive"))
      (node (ref "C228") (pin "1") (pinfunction "1_1") (pintype "passive"))
      (node (ref "D200") (pin "C") (pinfunction "K_C") (pintype "passive"))
      (node (ref "D202") (pin "C") (pinfunction "K_C") (pintype "passive"))
      (node (ref "R207") (pin "2") (pinfunction "2_2") (pintype "passive"))
      (node (ref "R231") (pin "2") (pinfunction "2_2") (pintype "passive"))
      (node (ref "RL200") (pin "A1") (pinfunction "COIL1_A1") (pintype "passive"))
      (node (ref "RL201") (pin "A1") (pinfunction "COIL1_A1") (pintype "passive"))
      (node (ref "U200") (pin "4") (pinfunction "CT_4") (pintype "passive"))
      (node (ref "U203") (pin "7") (pinfunction "+VOUT_7") (pintype "passive"))
      (node (ref "U206") (pin "4") (pinfunction "CT_4") (pintype "passive"))
    )
    (net (code "23") (name "GND") (class "Default")
      (node (ref "*") (pin "2") (pinfunction "V-_2") (pintype "power_in"))
      (node (ref "C200") (pin "1") (pinfunction "1_1") (pintype "passive"))
      (node (ref "C201") (pin "1") (pinfunction "1_1") (pintype "passive"))
      (node (ref "C213") (pin "1") (pinfunction "1_1") (pintype "passive"))
      (node (ref "C218") (pin "2") (pinfunction "2_2") (pintype "passive"))
      (node (ref "C219") (pin "1") (pinfunction "1_1") (pintype "passive"))
      (node (ref "C220") (pin "1") (pinfunction "1_1") (pintype "passive"))
      (node (ref "C221") (pin "1") (pinfunction "1_1") (pintype "passive"))
      (node (ref "C222") (pin "1") (pinfunction "1_1") (pintype "passive"))
      (node (ref "C223") (pin "1") (pinfunction "1_1") (pintype "passive"))
      (node (ref "C225") (pin "2") (pinfunction "2_2") (pintype "passive"))
      (node (ref "C226") (pin "2") (pinfunction "2_2") (pintype "passive"))
      (node (ref "C229") (pin "1") (pinfunction "1_1") (pintype "passive"))
      (node (ref "C230") (pin "1") (pinfunction "1_1") (pintype "passive"))
      (node (ref "C231") (pin "1") (pinfunction "1_1") (pintype "passive"))
      (node (ref "C232") (pin "1") (pinfunction "1_1") (pintype "passive"))
      (node (ref "C233") (pin "2") (pinfunction "2_2") (pintype "passive"))
      (node (ref "FB200") (pin "1") (pinfunction "1_1") (pintype "passive"))
      (node (ref "H202") (pin "2") (pinfunction "2_2") (pintype "passive"))
      (node (ref "R205") (pin "1") (pinfunction "1_1") (pintype "passive"))
      (node (ref "R218") (pin "1") (pinfunction "1_1") (pintype "passive"))
      (node (ref "R221") (pin "1") (pinfunction "1_1") (pintype "passive"))
      (node (ref "R225") (pin "1") (pinfunction "1_1") (pintype "passive"))
      (node (ref "R226") (pin "1") (pinfunction "1_1") (pintype "passive"))
      (node (ref "R230") (pin "1") (pinfunction "1_1") (pintype "passive"))
      (node (ref "TVS200") (pin "2") (pinfunction "A_2") (pintype "passive"))
      (node (ref "TVS201") (pin "2") (pinfunction "A_2") (pintype "passive"))
      (node (ref "U15") (pin "4") (pinfunction "-_4") (pintype "passive"))
      (node (ref "U201") (pin "4") (pinfunction "GND_4") (pintype "passive"))
      (node (ref "U202") (pin "4") (pinfunction "VSS_4") (pintype "passive"))
      (node (ref "U203") (pin "2") (pinfunction "-VIN_2") (pintype "passive"))
      (node (ref "U204") (pin "2") (pinfunction "GND_2") (pintype "power_in"))
      (node (ref "U205") (pin "2") (pinfunction "GND_2") (pintype "power_in"))
    )
    (net (code "24") (name "ISOGND") (class "Default")
      (node (ref "C227") (pin "2") (pinfunction "2_2") (pintype "passive"))
      (node (ref "C228") (pin "2") (pinfunction "2_2") (pintype "passive"))
      (node (ref "Q200") (pin "2") (pinfunction "E_2") (pintype "passive"))
      (node (ref "Q207") (pin "2") (pinfunction "E_2") (pintype "passive"))
      (node (ref "U203") (pin "5") (pinfunction "-VOUT_5") (pintype "passive"))
    )
    (net (code "25") (name "Net-(*-+IN)") (class "Default")
      (node (ref "*") (pin "3") (pinfunction "+IN_3") (pintype "input"))
      (node (ref "C216") (pin "2") (pinfunction "2_2") (pintype "passive"))
      (node (ref "C217") (pin "1") (pinfunction "1_1") (pintype "passive"))
      (node (ref "C218") (pin "1") (pinfunction "1_1") (pintype "passive"))
      (node (ref "R217") (pin "2") (pinfunction "2_2") (pintype "passive"))
      (node (ref "R218") (pin "2") (pinfunction "2_2") (pintype "passive"))
    )
    (net (code "26") (name "Net-(*--IN)") (class "Default")
      (node (ref "*") (pin "4") (pinfunction "-IN_4") (pintype "input"))
      (node (ref "C214") (pin "1") (pinfunction "1_1") (pintype "passive"))
      (node (ref "C215") (pin "1") (pinfunction "1_1") (pintype "passive"))
      (node (ref "C216") (pin "1") (pinfunction "1_1") (pintype "passive"))
      (node (ref "R214") (pin "2") (pinfunction "2_2") (pintype "passive"))
      (node (ref "R215") (pin "2") (pinfunction "2_2") (pintype "passive"))
    )
    (net (code "27") (name "Net-(B201-Pad1)") (class "Default")
      (node (ref "B201") (pin "1") (pinfunction "1_1") (pintype "passive"))
      (node (ref "R211") (pin "1") (pinfunction "1_1") (pintype "passive"))
      (node (ref "R212") (pin "1") (pinfunction "1_1") (pintype "passive"))
      (node (ref "R213") (pin "1") (pinfunction "1_1") (pintype "passive"))
      (node (ref "R216") (pin "1") (pinfunction "1_1") (pintype "passive"))
    )
    (net (code "28") (name "Net-(B202-Pad1)") (class "Default")
      (node (ref "B202") (pin "1") (pinfunction "1_1") (pintype "passive"))
      (node (ref "FB200") (pin "2") (pinfunction "2_2") (pintype "passive"))
    )
    (net (code "29") (name "Net-(C202-Pad2)") (class "Default")
      (node (ref "C202") (pin "2") (pinfunction "2_2") (pintype "passive"))
      (node (ref "R207") (pin "1") (pinfunction "1_1") (pintype "passive"))
    )
    (net (code "30") (name "Net-(C221-Pad2)") (class "Default")
      (node (ref "C221") (pin "2") (pinfunction "2_2") (pintype "passive"))
      (node (ref "R220") (pin "2") (pinfunction "2_2") (pintype "passive"))
    )
    (net (code "31") (name "Net-(C234-Pad2)") (class "Default")
      (node (ref "C234") (pin "2") (pinfunction "2_2") (pintype "passive"))
      (node (ref "R231") (pin "1") (pinfunction "1_1") (pintype "passive"))
    )
    (net (code "32") (name "Net-(D201-PadA)") (class "Default")
      (node (ref "D201") (pin "A") (pinfunction "A_A") (pintype "passive"))
      (node (ref "R222") (pin "1") (pinfunction "1_1") (pintype "passive"))
    )
    (net (code "33") (name "Net-(H201-Pad1)") (class "Default")
      (node (ref "H201") (pin "1") (pinfunction "1_1") (pintype "passive"))
      (node (ref "RL201") (pin "12-1") (pinfunction "NC_12-1") (pintype "passive"))
    )
    (net (code "34") (name "Net-(H201-Pad2)") (class "Default")
      (node (ref "H201") (pin "2") (pinfunction "2_2") (pintype "passive"))
      (node (ref "RL201") (pin "12-2") (pinfunction "NC_12-2") (pintype "passive"))
    )
    (net (code "35") (name "Net-(NTC200-Pad2)") (class "Default")
      (node (ref "NTC200") (pin "2") (pinfunction "2_2") (pintype "passive"))
      (node (ref "RL200") (pin "12-1") (pinfunction "NC_12-1") (pintype "passive"))
    )
    (net (code "36") (name "Net-(NTC201-Pad1)") (class "Default")
      (node (ref "NTC201") (pin "1") (pinfunction "1_1") (pintype "passive"))
      (node (ref "R229") (pin "2") (pinfunction "2_2") (pintype "passive"))
      (node (ref "R230") (pin "2") (pinfunction "2_2") (pintype "passive"))
    )
    (net (code "37") (name "Net-(Q200-B)") (class "Default")
      (node (ref "Q200") (pin "1") (pinfunction "B_1") (pintype "passive"))
      (node (ref "R201") (pin "2") (pinfunction "2_2") (pintype "passive"))
    )
    (net (code "38") (name "Net-(Q200-C)") (class "Default")
      (node (ref "C202") (pin "1") (pinfunction "1_1") (pintype "passive"))
      (node (ref "D200") (pin "A") (pinfunction "A_A") (pintype "passive"))
      (node (ref "Q200") (pin "3") (pinfunction "C_3") (pintype "passive"))
      (node (ref "RL200") (pin "A2") (pinfunction "COIL2_A2") (pintype "passive"))
    )
    (net (code "39") (name "Net-(Q201-D)") (class "Default")
      (node (ref "Q201") (pin "2") (pinfunction "D_2") (pintype "passive"))
      (node (ref "R208") (pin "1") (pinfunction "1_1") (pintype "passive"))
    )
    (net (code "40") (name "Net-(Q201-S)") (class "Default")
      (node (ref "Q201") (pin "3") (pinfunction "S_3") (pintype "passive"))
      (node (ref "Q202") (pin "3") (pinfunction "S_3") (pintype "passive"))
      (node (ref "Q203") (pin "3") (pinfunction "S_3") (pintype "passive"))
      (node (ref "U204") (pin "5") (pinfunction "IP-_5") (pintype "passive"))
    )
    (net (code "41") (name "Net-(Q202-D)") (class "Default")
      (node (ref "Q202") (pin "2") (pinfunction "D_2") (pintype "passive"))
      (node (ref "R209") (pin "1") (pinfunction "1_1") (pintype "passive"))
    )
    (net (code "42") (name "Net-(Q203-D)") (class "Default")
      (node (ref "Q203") (pin "2") (pinfunction "D_2") (pintype "passive"))
      (node (ref "R210") (pin "1") (pinfunction "1_1") (pintype "passive"))
    )
    (net (code "43") (name "Net-(Q204-S)") (class "Default")
      (node (ref "Q204") (pin "3") (pinfunction "S_3") (pintype "passive"))
      (node (ref "R211") (pin "2") (pinfunction "2_2") (pintype "passive"))
    )
    (net (code "44") (name "Net-(Q205-S)") (class "Default")
      (node (ref "Q205") (pin "3") (pinfunction "S_3") (pintype "passive"))
      (node (ref "R212") (pin "2") (pinfunction "2_2") (pintype "passive"))
    )
    (net (code "45") (name "Net-(Q206-S)") (class "Default")
      (node (ref "Q206") (pin "3") (pinfunction "S_3") (pintype "passive"))
      (node (ref "R213") (pin "2") (pinfunction "2_2") (pintype "passive"))
    )
    (net (code "46") (name "Net-(Q207-B)") (class "Default")
      (node (ref "Q207") (pin "1") (pinfunction "B_1") (pintype "passive"))
      (node (ref "R233") (pin "2") (pinfunction "2_2") (pintype "passive"))
    )
    (net (code "47") (name "Net-(Q207-C)") (class "Default")
      (node (ref "C234") (pin "1") (pinfunction "1_1") (pintype "passive"))
      (node (ref "D202") (pin "A") (pinfunction "A_A") (pintype "passive"))
      (node (ref "Q207") (pin "3") (pinfunction "C_3") (pintype "passive"))
      (node (ref "RL201") (pin "A2") (pinfunction "COIL2_A2") (pintype "passive"))
    )
    (net (code "48") (name "Net-(R234-Pad1)") (class "Default")
      (node (ref "R234") (pin "1") (pinfunction "1_1") (pintype "passive"))
      (node (ref "R235") (pin "2") (pinfunction "2_2") (pintype "passive"))
    )
    (net (code "49") (name "Net-(U15B-IN2+)") (class "Default")
      (node (ref "C233") (pin "1") (pinfunction "1_1") (pintype "passive"))
      (node (ref "R229") (pin "1") (pinfunction "1_1") (pintype "passive"))
      (node (ref "U15") (pin "5") (pinfunction "IN2+_5") (pintype "passive"))
    )
    (net (code "50") (name "Net-(U200-A)") (class "Default")
      (node (ref "R200") (pin "2") (pinfunction "2_2") (pintype "passive"))
      (node (ref "U200") (pin "1") (pinfunction "A_1") (pintype "passive"))
    )
    (net (code "51") (name "Net-(U200-ET)") (class "Default")
      (node (ref "R201") (pin "1") (pinfunction "1_1") (pintype "passive"))
      (node (ref "U200") (pin "3") (pinfunction "ET_3") (pintype "passive"))
    )
    (net (code "52") (name "Net-(U201A-1IN+)") (class "Default")
      (node (ref "R202") (pin "1") (pinfunction "1_1") (pintype "passive"))
      (node (ref "R204") (pin "2") (pinfunction "2_2") (pintype "passive"))
      (node (ref "U201") (pin "3") (pinfunction "1IN+_3") (pintype "passive"))
    )
    (net (code "53") (name "Net-(U201A-1OUT)") (class "Default")
      (node (ref "R202") (pin "2") (pinfunction "2_2") (pintype "passive"))
      (node (ref "R206") (pin "1") (pinfunction "1_1") (pintype "passive"))
      (node (ref "U201") (pin "1") (pinfunction "1OUT_1") (pintype "passive"))
    )
    (net (code "54") (name "Net-(U202-HB)") (class "Default")
      (node (ref "C224") (pin "2") (pinfunction "2_2") (pintype "passive"))
      (node (ref "D201") (pin "C") (pinfunction "C_C") (pintype "passive"))
      (node (ref "U202") (pin "8") (pinfunction "HB_8") (pintype "passive"))
    )
    (net (code "55") (name "Net-(U202-HO)") (class "Default")
      (node (ref "R223") (pin "2") (pinfunction "2_2") (pintype "passive"))
      (node (ref "U202") (pin "7") (pinfunction "HO_7") (pintype "passive"))
    )
    (net (code "56") (name "Net-(U202-LO)") (class "Default")
      (node (ref "R224") (pin "2") (pinfunction "2_2") (pintype "passive"))
      (node (ref "U202") (pin "5") (pinfunction "LO_5") (pintype "passive"))
    )
    (net (code "57") (name "Net-(U202-VDD)") (class "Default")
      (node (ref "C223") (pin "2") (pinfunction "2_2") (pintype "passive"))
      (node (ref "FB201") (pin "2") (pinfunction "2_2") (pintype "passive"))
      (node (ref "R222") (pin "2") (pinfunction "2_2") (pintype "passive"))
      (node (ref "U202") (pin "1") (pinfunction "VDD_1") (pintype "passive"))
    )
    (net (code "58") (name "Net-(U204-IP+)") (class "Default")
      (node (ref "RL200") (pin "12-2") (pinfunction "NC_12-2") (pintype "passive"))
      (node (ref "U204") (pin "4") (pinfunction "IP+_4") (pintype "passive"))
    )
    (net (code "59") (name "Net-(U204-VIOUT)") (class "Default")
      (node (ref "R227") (pin "2") (pinfunction "2_2") (pintype "passive"))
      (node (ref "U204") (pin "3") (pinfunction "VIOUT_3") (pintype "passive"))
    )
    (net (code "60") (name "Net-(U205-IP-)") (class "Default")
      (node (ref "LOAD") (pin "1") (pinfunction "1_1") (pintype "passive"))
      (node (ref "LOAD") (pin "2") (pinfunction "2_2") (pintype "passive"))
      (node (ref "LOAD") (pin "3") (pinfunction "3_3") (pintype "passive"))
      (node (ref "LOAD") (pin "4") (pinfunction "4_4") (pintype "passive"))
      (node (ref "LOAD") (pin "5") (pinfunction "5_5") (pintype "passive"))
      (node (ref "U205") (pin "5") (pinfunction "IP-_5") (pintype "passive"))
    )
    (net (code "61") (name "Net-(U205-VIOUT)") (class "Default")
      (node (ref "R228") (pin "2") (pinfunction "2_2") (pintype "passive"))
      (node (ref "U205") (pin "3") (pinfunction "VIOUT_3") (pintype "passive"))
    )
    (net (code "62") (name "Net-(U206-A)") (class "Default")
      (node (ref "R232") (pin "2") (pinfunction "2_2") (pintype "passive"))
      (node (ref "U206") (pin "1") (pinfunction "A_1") (pintype "passive"))
    )
    (net (code "63") (name "Net-(U206-ET)") (class "Default")
      (node (ref "R233") (pin "1") (pinfunction "1_1") (pintype "passive"))
      (node (ref "U206") (pin "3") (pinfunction "ET_3") (pintype "passive"))
    )
    (net (code "64") (name "PGND") (class "Default")
      (node (ref "B200") (pin "1") (pinfunction "1_1") (pintype "passive"))
      (node (ref "B202") (pin "2") (pinfunction "2_2") (pintype "passive"))
      (node (ref "C203") (pin "2") (pinfunction "2_2") (pintype "passive"))
      (node (ref "C204") (pin "2") (pinfunction "2_2") (pintype "passive"))
      (node (ref "C205") (pin "2") (pinfunction "2_2") (pintype "passive"))
      (node (ref "C206") (pin "2") (pinfunction "2_2") (pintype "passive"))
      (node (ref "C207") (pin "2") (pinfunction "2_2") (pintype "passive"))
      (node (ref "C208") (pin "2") (pinfunction "2_2") (pintype "passive"))
      (node (ref "C209") (pin "2") (pinfunction "2_2") (pintype "passive"))
      (node (ref "C210") (pin "2") (pinfunction "2_2") (pintype "passive"))
      (node (ref "C211") (pin "2") (pinfunction "2_2") (pintype "passive"))
      (node (ref "C212") (pin "2") (pinfunction "2_2") (pintype "passive"))
      (node (ref "R216") (pin "2") (pinfunction "2_2") (pintype "passive"))
      (node (ref "R236") (pin "1") (pinfunction "1_1") (pintype "passive"))
    )
    (net (code "65") (name "VOUT") (class "Default")
      (node (ref "BAT") (pin "1") (pinfunction "1_1") (pintype "passive"))
      (node (ref "BAT") (pin "2") (pinfunction "2_2") (pintype "passive"))
      (node (ref "BAT") (pin "3") (pinfunction "3_3") (pintype "passive"))
      (node (ref "BAT") (pin "4") (pinfunction "4_4") (pintype "passive"))
      (node (ref "BAT") (pin "5") (pinfunction "5_5") (pintype "passive"))
      (node (ref "C208") (pin "1") (pinfunction "1_1") (pintype "passive"))
      (node (ref "C209") (pin "1") (pinfunction "1_1") (pintype "passive"))
      (node (ref "C210") (pin "1") (pinfunction "1_1") (pintype "passive"))
      (node (ref "C211") (pin "1") (pinfunction "1_1") (pintype "passive"))
      (node (ref "C212") (pin "1") (pinfunction "1_1") (pintype "passive"))
      (node (ref "L200") (pin "2") (pinfunction "2_2") (pintype "passive"))
      (node (ref "R219") (pin "2") (pinfunction "2_2") (pintype "passive"))
      (node (ref "U205") (pin "4") (pinfunction "IP+_4") (pintype "passive"))
    )
  )
)
